# NGUYEN_LI.net
KiCad netlist of a schematic drawn in Altium Designer
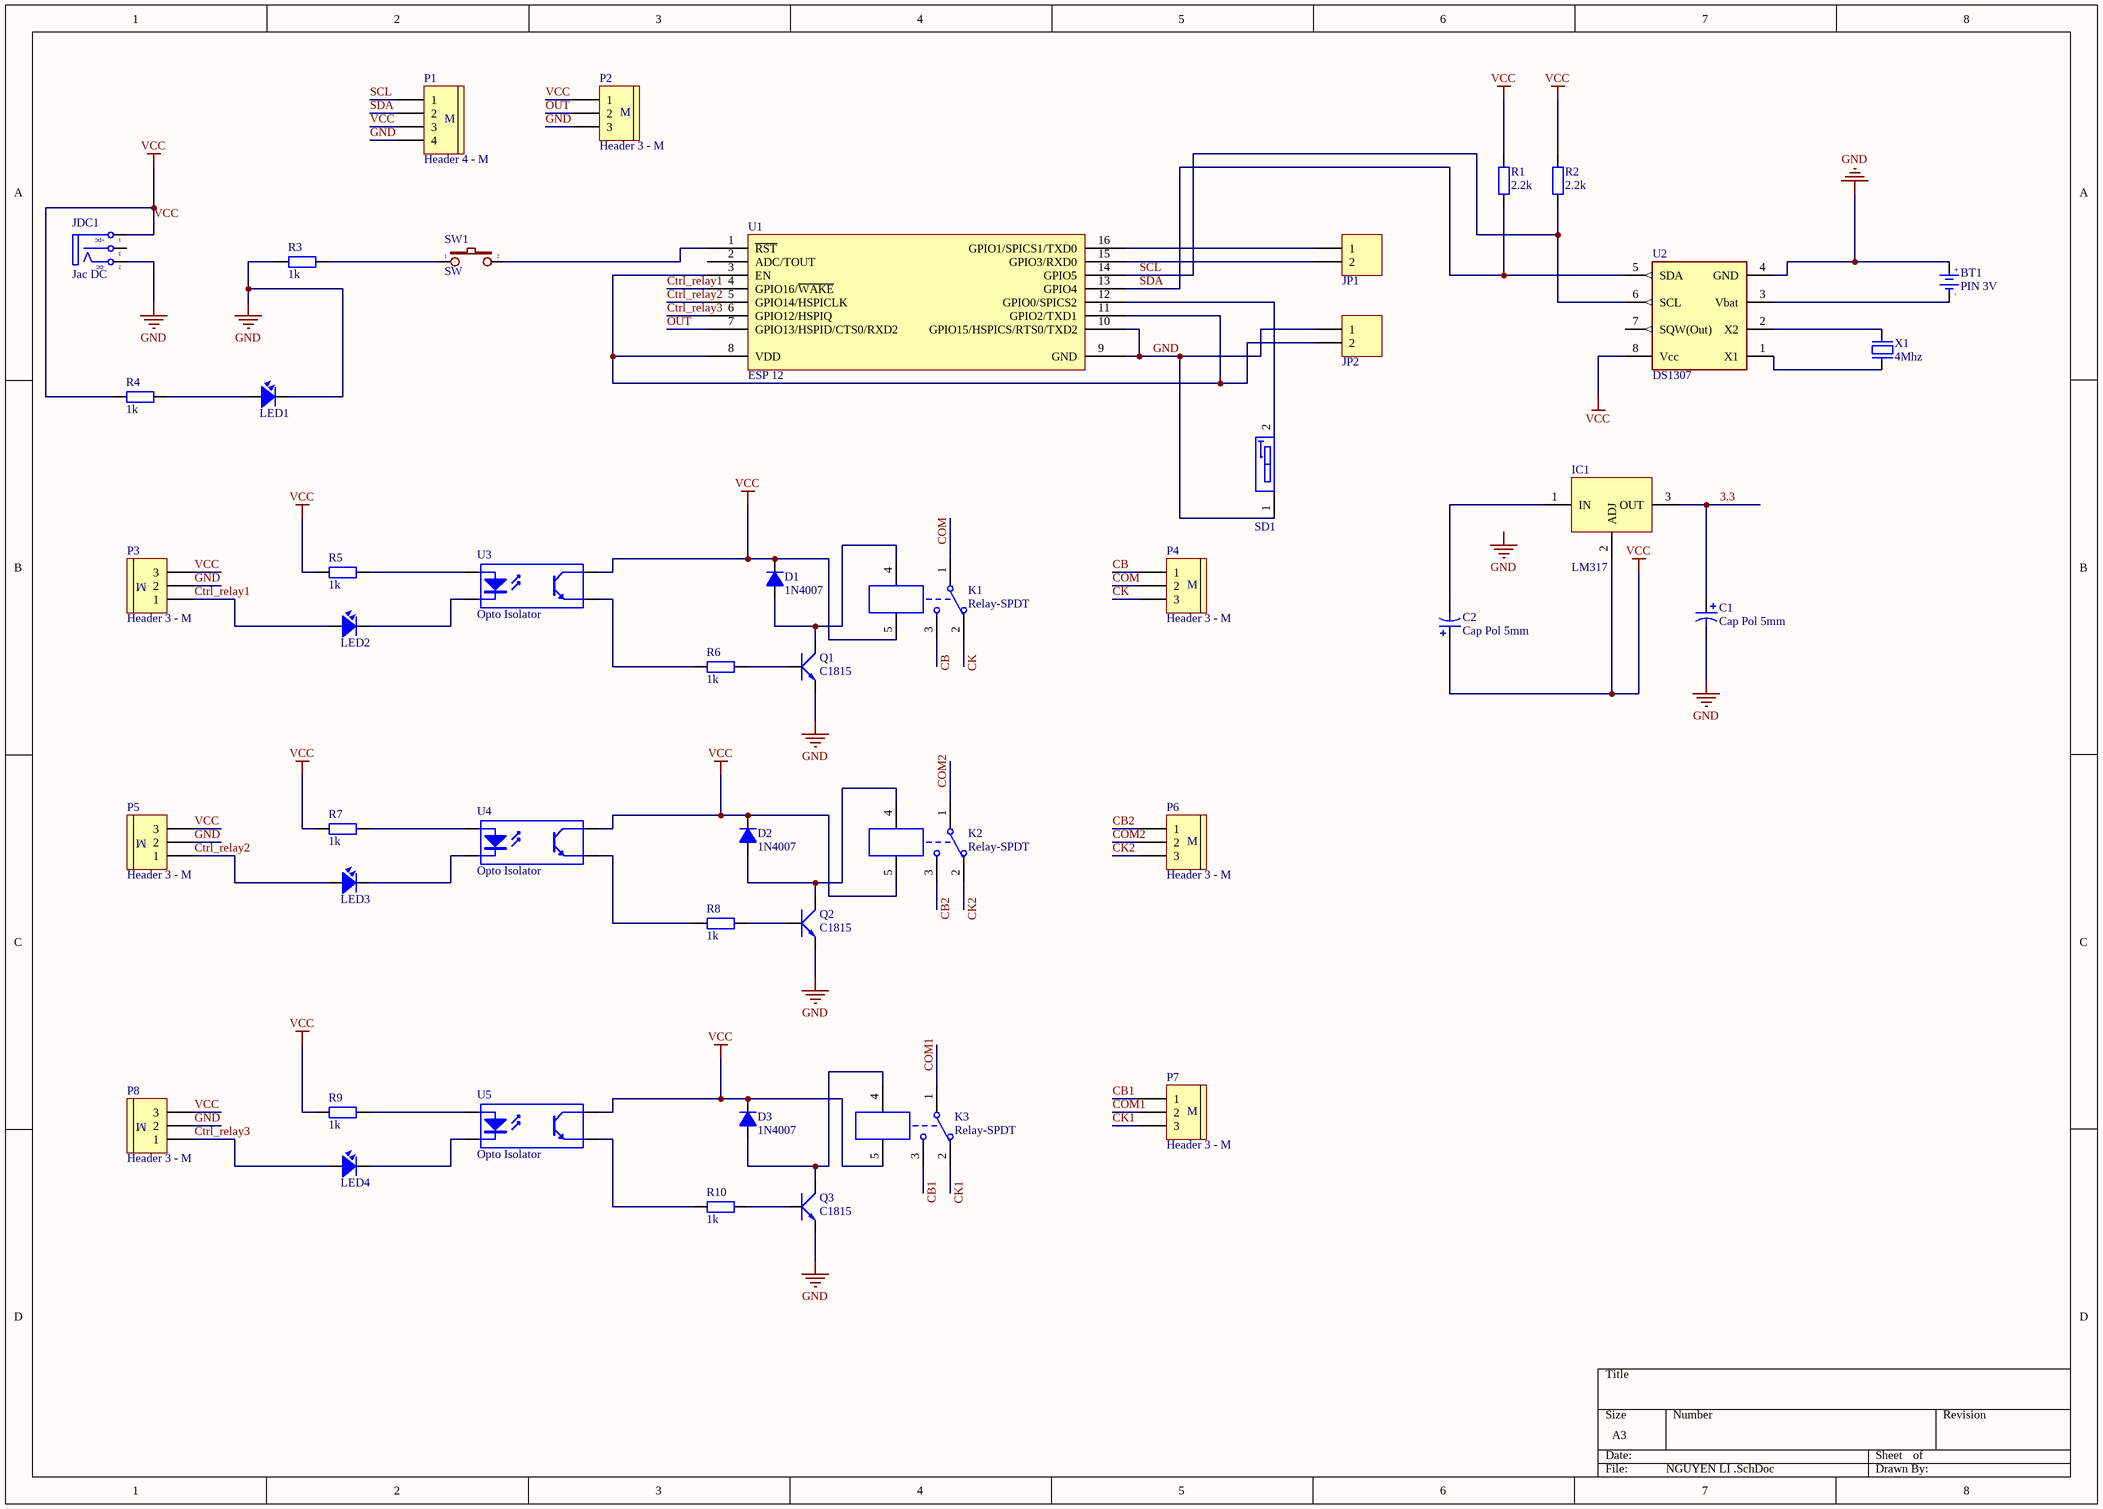
[diagram p0: NGUYEN LI .SchDoc]

(export (version "E")
  (design (tool "Eeschema 10.0.6"))
  (components
    (comp (ref "BT1")
      (value "PIN 3V")
      (footprint "PIN3V")
      (description "Battery 3VDC")
      (libsource (lib "syhaunguyen") (part "PIN 3V"))
    )
    (comp (ref "C1")
      (value "Cap Pol 5mm")
      (footprint "C5mm")
      (description "Polarized Capacitor (Axial)")
      (fields (field (name "PUBLISHER") "Altium Limited"))
      (libsource (lib "Devzone_SCHLib") (part "Cap Pol 5mm"))
    )
    (comp (ref "C2")
      (value "Cap Pol 5mm")
      (footprint "C5mm")
      (description "Polarized Capacitor (Axial)")
      (fields (field (name "PUBLISHER") "Altium Limited"))
      (libsource (lib "Devzone_SCHLib") (part "Cap Pol 5mm"))
    )
    (comp (ref "D1")
      (value "1N4007")
      (footprint "D2A")
      (description "Diode 1A")
      (libsource (lib "syhaunguyen") (part "D1A"))
    )
    (comp (ref "D2")
      (value "1N4007")
      (footprint "D2A")
      (description "Diode 1A")
      (libsource (lib "syhaunguyen") (part "D1A"))
    )
    (comp (ref "D3")
      (value "1N4007")
      (footprint "D2A")
      (description "Diode 1A")
      (libsource (lib "syhaunguyen") (part "D1A"))
    )
    (comp (ref "IC1")
      (value "LM317")
      (footprint "TO-220")
      (fields
        (field (name "CREATOR") "Nguyen Ba Bien")
        (field (name "CONTACT EMAIL") "bien-nb@thanglongie.com")
      )
      (libsource (lib "my Library") (part "LM317_1"))
    )
    (comp (ref "JDC1")
      (value "Jac DC")
      (footprint "DC-IN")
      (description "Jac DC input")
      (libsource (lib "syhaunguyen") (part "DCIN"))
    )
    (comp (ref "JP1")
      (value "Header 2_1")
      (footprint "HED2")
      (description "Header, 2-Pin")
      (fields (field (name "MANUFACTURER") "Generic Components"))
      (libsource (lib "syhaunguyen") (part "Header 2_1"))
    )
    (comp (ref "JP2")
      (value "Header 2_1")
      (footprint "HED2")
      (description "Header, 2-Pin")
      (fields (field (name "MANUFACTURER") "Generic Components"))
      (libsource (lib "syhaunguyen") (part "Header 2_1"))
    )
    (comp (ref "K1")
      (value "Relay-SPDT")
      (footprint "RELAY5PIN-10A")
      (description "Single-Pole Dual-Throw Relay")
      (fields (field (name "PUBLISHER") "Altium Limited"))
      (libsource (lib "My Library (1)") (part "Relay-SPDT"))
    )
    (comp (ref "K2")
      (value "Relay-SPDT")
      (footprint "RELAY5PIN-10A")
      (description "Single-Pole Dual-Throw Relay")
      (fields (field (name "PUBLISHER") "Altium Limited"))
      (libsource (lib "My Library (1)") (part "Relay-SPDT"))
    )
    (comp (ref "K3")
      (value "Relay-SPDT")
      (footprint "RELAY5PIN-10A")
      (description "Single-Pole Dual-Throw Relay")
      (fields (field (name "PUBLISHER") "Altium Limited"))
      (libsource (lib "My Library (1)") (part "Relay-SPDT"))
    )
    (comp (ref "LED1")
      (value "LED")
      (footprint "LED-3")
      (description "LED Single colour Green and Red")
      (libsource (lib "syhaunguyen") (part "LED"))
    )
    (comp (ref "LED2")
      (value "LED")
      (footprint "LED-3")
      (description "LED Single colour Green and Red")
      (libsource (lib "syhaunguyen") (part "LED"))
    )
    (comp (ref "LED3")
      (value "LED")
      (footprint "LED-3")
      (description "LED Single colour Green and Red")
      (libsource (lib "syhaunguyen") (part "LED"))
    )
    (comp (ref "LED4")
      (value "LED")
      (footprint "LED-3")
      (description "LED Single colour Green and Red")
      (libsource (lib "syhaunguyen") (part "LED"))
    )
    (comp (ref "P1")
      (value "Header 4 - M")
      (footprint "Medium - Header 4")
      (description "Header, 3-Pin, Medium")
      (fields (field (name "PUBLISHER") "Altium Limited"))
      (libsource (lib "BYTECH_HW_LIB_2019 (1) (1)") (part "Header 4 - M"))
    )
    (comp (ref "P2")
      (value "Header 3 - M")
      (footprint "Medium - Header 3")
      (description "Header, 3-Pin, Medium")
      (fields (field (name "PUBLISHER") "Altium Limited"))
      (libsource (lib "") (part "Header 3 - M_1"))
    )
    (comp (ref "P3")
      (value "Header 3 - M")
      (footprint "Medium - Header 3")
      (description "Header, 3-Pin, Medium")
      (fields (field (name "PUBLISHER") "Altium Limited"))
      (libsource (lib "BYTECH_HW_LIB_2019 (1) (1)") (part "Header 3 - M"))
    )
    (comp (ref "P4")
      (value "Header 3 - M")
      (footprint "Medium - Header 3")
      (description "Header, 3-Pin, Medium")
      (fields (field (name "PUBLISHER") "Altium Limited"))
      (libsource (lib "") (part "Header 3 - M_1"))
    )
    (comp (ref "P5")
      (value "Header 3 - M")
      (footprint "Medium - Header 3")
      (description "Header, 3-Pin, Medium")
      (fields (field (name "PUBLISHER") "Altium Limited"))
      (libsource (lib "BYTECH_HW_LIB_2019 (1) (1)") (part "Header 3 - M"))
    )
    (comp (ref "P6")
      (value "Header 3 - M")
      (footprint "Medium - Header 3")
      (description "Header, 3-Pin, Medium")
      (fields (field (name "PUBLISHER") "Altium Limited"))
      (libsource (lib "") (part "Header 3 - M_1"))
    )
    (comp (ref "P7")
      (value "Header 3 - M")
      (footprint "Medium - Header 3")
      (description "Header, 3-Pin, Medium")
      (fields (field (name "PUBLISHER") "Altium Limited"))
      (libsource (lib "") (part "Header 3 - M_1"))
    )
    (comp (ref "P8")
      (value "Header 3 - M")
      (footprint "Medium - Header 3")
      (description "Header, 3-Pin, Medium")
      (fields (field (name "PUBLISHER") "Altium Limited"))
      (libsource (lib "BYTECH_HW_LIB_2019 (1) (1)") (part "Header 3 - M"))
    )
    (comp (ref "Q1")
      (value "C1815")
      (footprint "QTO-92")
      (description "NPN 600mW, ECB")
      (libsource (lib "syhaunguyen") (part "C1815"))
    )
    (comp (ref "Q2")
      (value "C1815")
      (footprint "QTO-92")
      (description "NPN 600mW, ECB")
      (libsource (lib "syhaunguyen") (part "C1815"))
    )
    (comp (ref "Q3")
      (value "C1815")
      (footprint "QTO-92")
      (description "NPN 600mW, ECB")
      (libsource (lib "syhaunguyen") (part "C1815"))
    )
    (comp (ref "R1")
      (value "2.2k")
      (footprint "R1/4W")
      (description "Resistor 1/4W")
      (libsource (lib "My Library (1)") (part "R1/4W"))
    )
    (comp (ref "R2")
      (value "2.2k")
      (footprint "R1/4W")
      (description "Resistor 1/4W")
      (libsource (lib "My Library (1)") (part "R1/4W"))
    )
    (comp (ref "R3")
      (value "1k")
      (footprint "R1/4W")
      (description "Resistor 1/4W")
      (libsource (lib "Devzone_SCHLib") (part "R1/4W"))
    )
    (comp (ref "R4")
      (value "1k")
      (footprint "R1/4W")
      (description "Resistor 1/4W")
      (libsource (lib "Devzone_SCHLib") (part "R1/4W"))
    )
    (comp (ref "R5")
      (value "1k")
      (footprint "R1/4W")
      (description "Resistor 1/4W")
      (libsource (lib "Devzone_SCHLib") (part "R1/4W"))
    )
    (comp (ref "R6")
      (value "1k")
      (footprint "R1/4W")
      (description "Resistor 1/4W")
      (libsource (lib "Devzone_SCHLib") (part "R1/4W"))
    )
    (comp (ref "R7")
      (value "1k")
      (footprint "R1/4W")
      (description "Resistor 1/4W")
      (libsource (lib "Devzone_SCHLib") (part "R1/4W"))
    )
    (comp (ref "R8")
      (value "1k")
      (footprint "R1/4W")
      (description "Resistor 1/4W")
      (libsource (lib "Devzone_SCHLib") (part "R1/4W"))
    )
    (comp (ref "R9")
      (value "1k")
      (footprint "R1/4W")
      (description "Resistor 1/4W")
      (libsource (lib "Devzone_SCHLib") (part "R1/4W"))
    )
    (comp (ref "R10")
      (value "1k")
      (footprint "R1/4W")
      (description "Resistor 1/4W")
      (libsource (lib "Devzone_SCHLib") (part "R1/4W"))
    )
    (comp (ref "SD1")
      (value "SW - DIP2")
      (footprint "DIP2/W0.3K")
      (description "DIP Switch, 2 Position, SPST")
      (libsource (lib "my Library") (part "SWDIP-1"))
    )
    (comp (ref "SW1")
      (value "SW")
      (footprint "BUTTON 2PIN TRON")
      (description "Switch button 2 pin")
      (libsource (lib "SCH_MyLib_0") (part "SW2"))
    )
    (comp (ref "U1")
      (value "ESP 12")
      (footprint "ESP12_small")
      (description "ESP-12 Wi-Fi Module by AI-Thinker")
      (libsource (lib "My Library (1)") (part "ESP_12"))
    )
    (comp (ref "U2")
      (value "DS1307")
      (footprint "DIP.100/8/W.300/L.400")
      (description "64 X 8 Serial Real-Time Clock")
      (libsource (lib "Cty1") (part "DS1307"))
    )
    (comp (ref "U3")
      (value "Opto Isolator")
      (footprint "PhotoCoupler")
      (description "4-Pin Phototransistor Optocoupler")
      (fields (field (name "PUBLISHER") "Altium Limited"))
      (libsource (lib "My Library (1)") (part "Opto Isolator"))
    )
    (comp (ref "U4")
      (value "Opto Isolator")
      (footprint "PhotoCoupler")
      (description "4-Pin Phototransistor Optocoupler")
      (fields (field (name "PUBLISHER") "Altium Limited"))
      (libsource (lib "My Library (1)") (part "Opto Isolator"))
    )
    (comp (ref "U5")
      (value "Opto Isolator")
      (footprint "PhotoCoupler")
      (description "4-Pin Phototransistor Optocoupler")
      (fields (field (name "PUBLISHER") "Altium Limited"))
      (libsource (lib "My Library (1)") (part "Opto Isolator"))
    )
    (comp (ref "X1")
      (value "4Mhz")
      (footprint "XT2")
      (description "Crystal For all Crystal 2pin.")
      (libsource (lib "syhaunguyen") (part "XT2"))
    )
  )
  (nets
    (net (code "1") (name "/3.3") (class "Default")
      (node (ref "C1") (pin "1") (pinfunction "1_1") (pintype "passive"))
      (node (ref "IC1") (pin "3") (pinfunction "OUT_3") (pintype "passive"))
    )
    (net (code "2") (name "/CB") (class "Default")
      (node (ref "K1") (pin "3") (pinfunction "3_3") (pintype "passive"))
      (node (ref "P4") (pin "1") (pinfunction "1_1") (pintype "passive"))
    )
    (net (code "3") (name "/CB1") (class "Default")
      (node (ref "K3") (pin "3") (pinfunction "3_3") (pintype "passive"))
      (node (ref "P7") (pin "1") (pinfunction "1_1") (pintype "passive"))
    )
    (net (code "4") (name "/CB2") (class "Default")
      (node (ref "K2") (pin "3") (pinfunction "3_3") (pintype "passive"))
      (node (ref "P6") (pin "1") (pinfunction "1_1") (pintype "passive"))
    )
    (net (code "5") (name "/CK") (class "Default")
      (node (ref "K1") (pin "2") (pinfunction "2_2") (pintype "passive"))
      (node (ref "P4") (pin "3") (pinfunction "3_3") (pintype "passive"))
    )
    (net (code "6") (name "/CK1") (class "Default")
      (node (ref "K3") (pin "2") (pinfunction "2_2") (pintype "passive"))
      (node (ref "P7") (pin "3") (pinfunction "3_3") (pintype "passive"))
    )
    (net (code "7") (name "/CK2") (class "Default")
      (node (ref "K2") (pin "2") (pinfunction "2_2") (pintype "passive"))
      (node (ref "P6") (pin "3") (pinfunction "3_3") (pintype "passive"))
    )
    (net (code "8") (name "/COM") (class "Default")
      (node (ref "K1") (pin "1") (pinfunction "1_1") (pintype "passive"))
      (node (ref "P4") (pin "2") (pinfunction "2_2") (pintype "passive"))
    )
    (net (code "9") (name "/COM1") (class "Default")
      (node (ref "K3") (pin "1") (pinfunction "1_1") (pintype "passive"))
      (node (ref "P7") (pin "2") (pinfunction "2_2") (pintype "passive"))
    )
    (net (code "10") (name "/COM2") (class "Default")
      (node (ref "K2") (pin "1") (pinfunction "1_1") (pintype "passive"))
      (node (ref "P6") (pin "2") (pinfunction "2_2") (pintype "passive"))
    )
    (net (code "11") (name "/Ctrl_relay1") (class "Default")
      (node (ref "LED2") (pin "1") (pinfunction "1_1") (pintype "passive"))
      (node (ref "P3") (pin "1") (pinfunction "1_1") (pintype "passive"))
      (node (ref "U1") (pin "4") (pinfunction "GPIO16/~{WAKE}_4") (pintype "passive"))
    )
    (net (code "12") (name "/Ctrl_relay2") (class "Default")
      (node (ref "LED3") (pin "1") (pinfunction "1_1") (pintype "passive"))
      (node (ref "P5") (pin "1") (pinfunction "1_1") (pintype "passive"))
      (node (ref "U1") (pin "5") (pinfunction "GPIO14/HSPICLK_5") (pintype "passive"))
    )
    (net (code "13") (name "/Ctrl_relay3") (class "Default")
      (node (ref "LED4") (pin "1") (pinfunction "1_1") (pintype "passive"))
      (node (ref "P8") (pin "1") (pinfunction "1_1") (pintype "passive"))
      (node (ref "U1") (pin "6") (pinfunction "GPIO12/HSPIQ_6") (pintype "passive"))
    )
    (net (code "14") (name "/OUT") (class "Default")
      (node (ref "P2") (pin "2") (pinfunction "2_2") (pintype "passive"))
      (node (ref "U1") (pin "7") (pinfunction "GPIO13/HSPID/CTS0/RXD2_7") (pintype "passive"))
    )
    (net (code "15") (name "/SCL") (class "Default")
      (node (ref "P1") (pin "1") (pinfunction "1_1") (pintype "passive"))
      (node (ref "R2") (pin "1") (pinfunction "1_1") (pintype "passive"))
      (node (ref "U1") (pin "14") (pinfunction "GPIO5_14") (pintype "passive"))
      (node (ref "U2") (pin "6") (pinfunction "SCL_6") (pintype "output"))
    )
    (net (code "16") (name "/SDA") (class "Default")
      (node (ref "P1") (pin "2") (pinfunction "2_2") (pintype "passive"))
      (node (ref "R1") (pin "2") (pinfunction "2_2") (pintype "passive"))
      (node (ref "U1") (pin "13") (pinfunction "GPIO4_13") (pintype "passive"))
      (node (ref "U2") (pin "5") (pinfunction "SDA_5") (pintype "output"))
    )
    (net (code "17") (name "GND") (class "Default")
      (node (ref "BT1") (pin "1") (pinfunction "+3V_1") (pintype "passive"))
      (node (ref "C1") (pin "2") (pinfunction "2_2") (pintype "passive"))
      (node (ref "JDC1") (pin "2") (pinfunction "TN_2") (pintype "passive"))
      (node (ref "JP2") (pin "1") (pinfunction "1_1") (pintype "passive"))
      (node (ref "LED1") (pin "2") (pinfunction "2_2") (pintype "passive"))
      (node (ref "P1") (pin "4") (pinfunction "4_4") (pintype "passive"))
      (node (ref "P2") (pin "3") (pinfunction "3_3") (pintype "passive"))
      (node (ref "P3") (pin "2") (pinfunction "2_2") (pintype "passive"))
      (node (ref "P5") (pin "2") (pinfunction "2_2") (pintype "passive"))
      (node (ref "P8") (pin "2") (pinfunction "2_2") (pintype "passive"))
      (node (ref "Q1") (pin "1") (pinfunction "E_1") (pintype "passive"))
      (node (ref "Q2") (pin "1") (pinfunction "E_1") (pintype "passive"))
      (node (ref "Q3") (pin "1") (pinfunction "E_1") (pintype "passive"))
      (node (ref "R3") (pin "1") (pinfunction "1_1") (pintype "passive"))
      (node (ref "SD1") (pin "1") (pinfunction "A1_1") (pintype "passive"))
      (node (ref "U1") (pin "10") (pinfunction "GPIO15/HSPICS/RTS0/TXD2_10") (pintype "passive"))
      (node (ref "U1") (pin "9") (pinfunction "GND_9") (pintype "passive"))
      (node (ref "U2") (pin "4") (pinfunction "GND_4") (pintype "power_in"))
    )
    (net (code "18") (name "Net-(BT1-GND)") (class "Default")
      (node (ref "BT1") (pin "2") (pinfunction "GND_2") (pintype "passive"))
      (node (ref "U2") (pin "3") (pinfunction "Vbat_3") (pintype "passive"))
    )
    (net (code "19") (name "Net-(D1-A)") (class "Default")
      (node (ref "D1") (pin "1") (pinfunction "A_1") (pintype "passive"))
      (node (ref "K1") (pin "4") (pinfunction "4_4") (pintype "passive"))
      (node (ref "Q1") (pin "2") (pinfunction "C_2") (pintype "passive"))
    )
    (net (code "20") (name "Net-(D2-A)") (class "Default")
      (node (ref "D2") (pin "1") (pinfunction "A_1") (pintype "passive"))
      (node (ref "K2") (pin "4") (pinfunction "4_4") (pintype "passive"))
      (node (ref "Q2") (pin "2") (pinfunction "C_2") (pintype "passive"))
    )
    (net (code "21") (name "Net-(D3-A)") (class "Default")
      (node (ref "D3") (pin "1") (pinfunction "A_1") (pintype "passive"))
      (node (ref "K3") (pin "4") (pinfunction "4_4") (pintype "passive"))
      (node (ref "Q3") (pin "2") (pinfunction "C_2") (pintype "passive"))
    )
    (net (code "22") (name "Net-(IC1-IN)") (class "Default")
      (node (ref "C2") (pin "2") (pinfunction "2_2") (pintype "passive"))
      (node (ref "IC1") (pin "1") (pinfunction "IN_1") (pintype "passive"))
    )
    (net (code "23") (name "Net-(LED1-Pad1)") (class "Default")
      (node (ref "LED1") (pin "1") (pinfunction "1_1") (pintype "passive"))
      (node (ref "R4") (pin "2") (pinfunction "2_2") (pintype "passive"))
    )
    (net (code "24") (name "Net-(Q1-B)") (class "Default")
      (node (ref "Q1") (pin "3") (pinfunction "B_3") (pintype "passive"))
      (node (ref "R6") (pin "2") (pinfunction "2_2") (pintype "passive"))
    )
    (net (code "25") (name "Net-(Q2-B)") (class "Default")
      (node (ref "Q2") (pin "3") (pinfunction "B_3") (pintype "passive"))
      (node (ref "R8") (pin "2") (pinfunction "2_2") (pintype "passive"))
    )
    (net (code "26") (name "Net-(Q3-B)") (class "Default")
      (node (ref "Q3") (pin "3") (pinfunction "B_3") (pintype "passive"))
      (node (ref "R10") (pin "2") (pinfunction "2_2") (pintype "passive"))
    )
    (net (code "27") (name "Net-(R3-Pad2)") (class "Default")
      (node (ref "R3") (pin "2") (pinfunction "2_2") (pintype "passive"))
      (node (ref "SW1") (pin "1") (pinfunction "1_1") (pintype "passive"))
    )
    (net (code "28") (name "Net-(SD1-A2)") (class "Default")
      (node (ref "SD1") (pin "2") (pinfunction "A2_2") (pintype "passive"))
      (node (ref "U1") (pin "12") (pinfunction "GPIO0/SPICS2_12") (pintype "passive"))
    )
    (net (code "29") (name "Net-(U1-EN)") (class "Default")
      (node (ref "JP2") (pin "2") (pinfunction "2_2") (pintype "passive"))
      (node (ref "U1") (pin "11") (pinfunction "GPIO2/TXD1_11") (pintype "passive"))
      (node (ref "U1") (pin "3") (pinfunction "EN_3") (pintype "passive"))
      (node (ref "U1") (pin "8") (pinfunction "VDD_8") (pintype "passive"))
    )
    (net (code "30") (name "Net-(U1-GPIO1{slash}SPICS1{slash}TXD0)") (class "Default")
      (node (ref "JP1") (pin "1") (pinfunction "1_1") (pintype "passive"))
      (node (ref "U1") (pin "16") (pinfunction "GPIO1/SPICS1/TXD0_16") (pintype "passive"))
    )
    (net (code "31") (name "Net-(U1-GPIO3{slash}RXD0)") (class "Default")
      (node (ref "JP1") (pin "2") (pinfunction "2_2") (pintype "passive"))
      (node (ref "U1") (pin "15") (pinfunction "GPIO3/RXD0_15") (pintype "passive"))
    )
    (net (code "32") (name "Net-(U1-~{RST})") (class "Default")
      (node (ref "SW1") (pin "2") (pinfunction "2_2") (pintype "passive"))
      (node (ref "U1") (pin "1") (pinfunction "~{RST}_1") (pintype "passive"))
    )
    (net (code "33") (name "Net-(U2-X1)") (class "Default")
      (node (ref "U2") (pin "1") (pinfunction "X1_1") (pintype "passive"))
      (node (ref "X1") (pin "1") (pinfunction "1_1") (pintype "passive"))
    )
    (net (code "34") (name "Net-(U2-X2)") (class "Default")
      (node (ref "U2") (pin "2") (pinfunction "X2_2") (pintype "passive"))
      (node (ref "X1") (pin "2") (pinfunction "2_2") (pintype "passive"))
    )
    (net (code "35") (name "Net-(U3-A)") (class "Default")
      (node (ref "R5") (pin "2") (pinfunction "2_2") (pintype "passive"))
      (node (ref "U3") (pin "1") (pinfunction "A_1") (pintype "passive"))
    )
    (net (code "36") (name "Net-(U3-E)") (class "Default")
      (node (ref "R6") (pin "1") (pinfunction "1_1") (pintype "passive"))
      (node (ref "U3") (pin "3") (pinfunction "E_3") (pintype "passive"))
    )
    (net (code "37") (name "Net-(U3-K)") (class "Default")
      (node (ref "LED2") (pin "2") (pinfunction "2_2") (pintype "passive"))
      (node (ref "U3") (pin "2") (pinfunction "K_2") (pintype "passive"))
    )
    (net (code "38") (name "Net-(U4-A)") (class "Default")
      (node (ref "R7") (pin "2") (pinfunction "2_2") (pintype "passive"))
      (node (ref "U4") (pin "1") (pinfunction "A_1") (pintype "passive"))
    )
    (net (code "39") (name "Net-(U4-E)") (class "Default")
      (node (ref "R8") (pin "1") (pinfunction "1_1") (pintype "passive"))
      (node (ref "U4") (pin "3") (pinfunction "E_3") (pintype "passive"))
    )
    (net (code "40") (name "Net-(U4-K)") (class "Default")
      (node (ref "LED3") (pin "2") (pinfunction "2_2") (pintype "passive"))
      (node (ref "U4") (pin "2") (pinfunction "K_2") (pintype "passive"))
    )
    (net (code "41") (name "Net-(U5-A)") (class "Default")
      (node (ref "R9") (pin "2") (pinfunction "2_2") (pintype "passive"))
      (node (ref "U5") (pin "1") (pinfunction "A_1") (pintype "passive"))
    )
    (net (code "42") (name "Net-(U5-E)") (class "Default")
      (node (ref "R10") (pin "1") (pinfunction "1_1") (pintype "passive"))
      (node (ref "U5") (pin "3") (pinfunction "E_3") (pintype "passive"))
    )
    (net (code "43") (name "Net-(U5-K)") (class "Default")
      (node (ref "LED4") (pin "2") (pinfunction "2_2") (pintype "passive"))
      (node (ref "U5") (pin "2") (pinfunction "K_2") (pintype "passive"))
    )
    (net (code "44") (name "VCC") (class "Default")
      (node (ref "C2") (pin "1") (pinfunction "1_1") (pintype "passive"))
      (node (ref "D1") (pin "2") (pinfunction "K_2") (pintype "passive"))
      (node (ref "D2") (pin "2") (pinfunction "K_2") (pintype "passive"))
      (node (ref "D3") (pin "2") (pinfunction "K_2") (pintype "passive"))
      (node (ref "IC1") (pin "2") (pinfunction "ADJ_2") (pintype "passive"))
      (node (ref "JDC1") (pin "1") (pinfunction "T_1") (pintype "passive"))
      (node (ref "K1") (pin "5") (pinfunction "5_5") (pintype "passive"))
      (node (ref "K2") (pin "5") (pinfunction "5_5") (pintype "passive"))
      (node (ref "K3") (pin "5") (pinfunction "5_5") (pintype "passive"))
      (node (ref "P1") (pin "3") (pinfunction "3_3") (pintype "passive"))
      (node (ref "P2") (pin "1") (pinfunction "1_1") (pintype "passive"))
      (node (ref "P3") (pin "3") (pinfunction "3_3") (pintype "passive"))
      (node (ref "P5") (pin "3") (pinfunction "3_3") (pintype "passive"))
      (node (ref "P8") (pin "3") (pinfunction "3_3") (pintype "passive"))
      (node (ref "R1") (pin "1") (pinfunction "1_1") (pintype "passive"))
      (node (ref "R2") (pin "2") (pinfunction "2_2") (pintype "passive"))
      (node (ref "R4") (pin "1") (pinfunction "1_1") (pintype "passive"))
      (node (ref "R5") (pin "1") (pinfunction "1_1") (pintype "passive"))
      (node (ref "R7") (pin "1") (pinfunction "1_1") (pintype "passive"))
      (node (ref "R9") (pin "1") (pinfunction "1_1") (pintype "passive"))
      (node (ref "U2") (pin "8") (pinfunction "Vcc_8") (pintype "power_in"))
      (node (ref "U3") (pin "4") (pinfunction "C_4") (pintype "passive"))
      (node (ref "U4") (pin "4") (pinfunction "C_4") (pintype "passive"))
      (node (ref "U5") (pin "4") (pinfunction "C_4") (pintype "passive"))
    )
    (net (code "45") (name "unconnected-(JDC1-S-Pad3)") (class "Default")
      (node (ref "JDC1") (pin "3") (pinfunction "S_3") (pintype "power_in"))
    )
    (net (code "46") (name "unconnected-(U1-ADC{slash}TOUT-Pad2)") (class "Default")
      (node (ref "U1") (pin "2") (pinfunction "ADC/TOUT_2") (pintype "passive"))
    )
    (net (code "47") (name "unconnected-(U2-SQW(Out)-Pad7)") (class "Default")
      (node (ref "U2") (pin "7") (pinfunction "SQW(Out)_7") (pintype "output"))
    )
  )
)
